# kicik-up.net
KiCad netlist of a schematic drawn in EAGLE
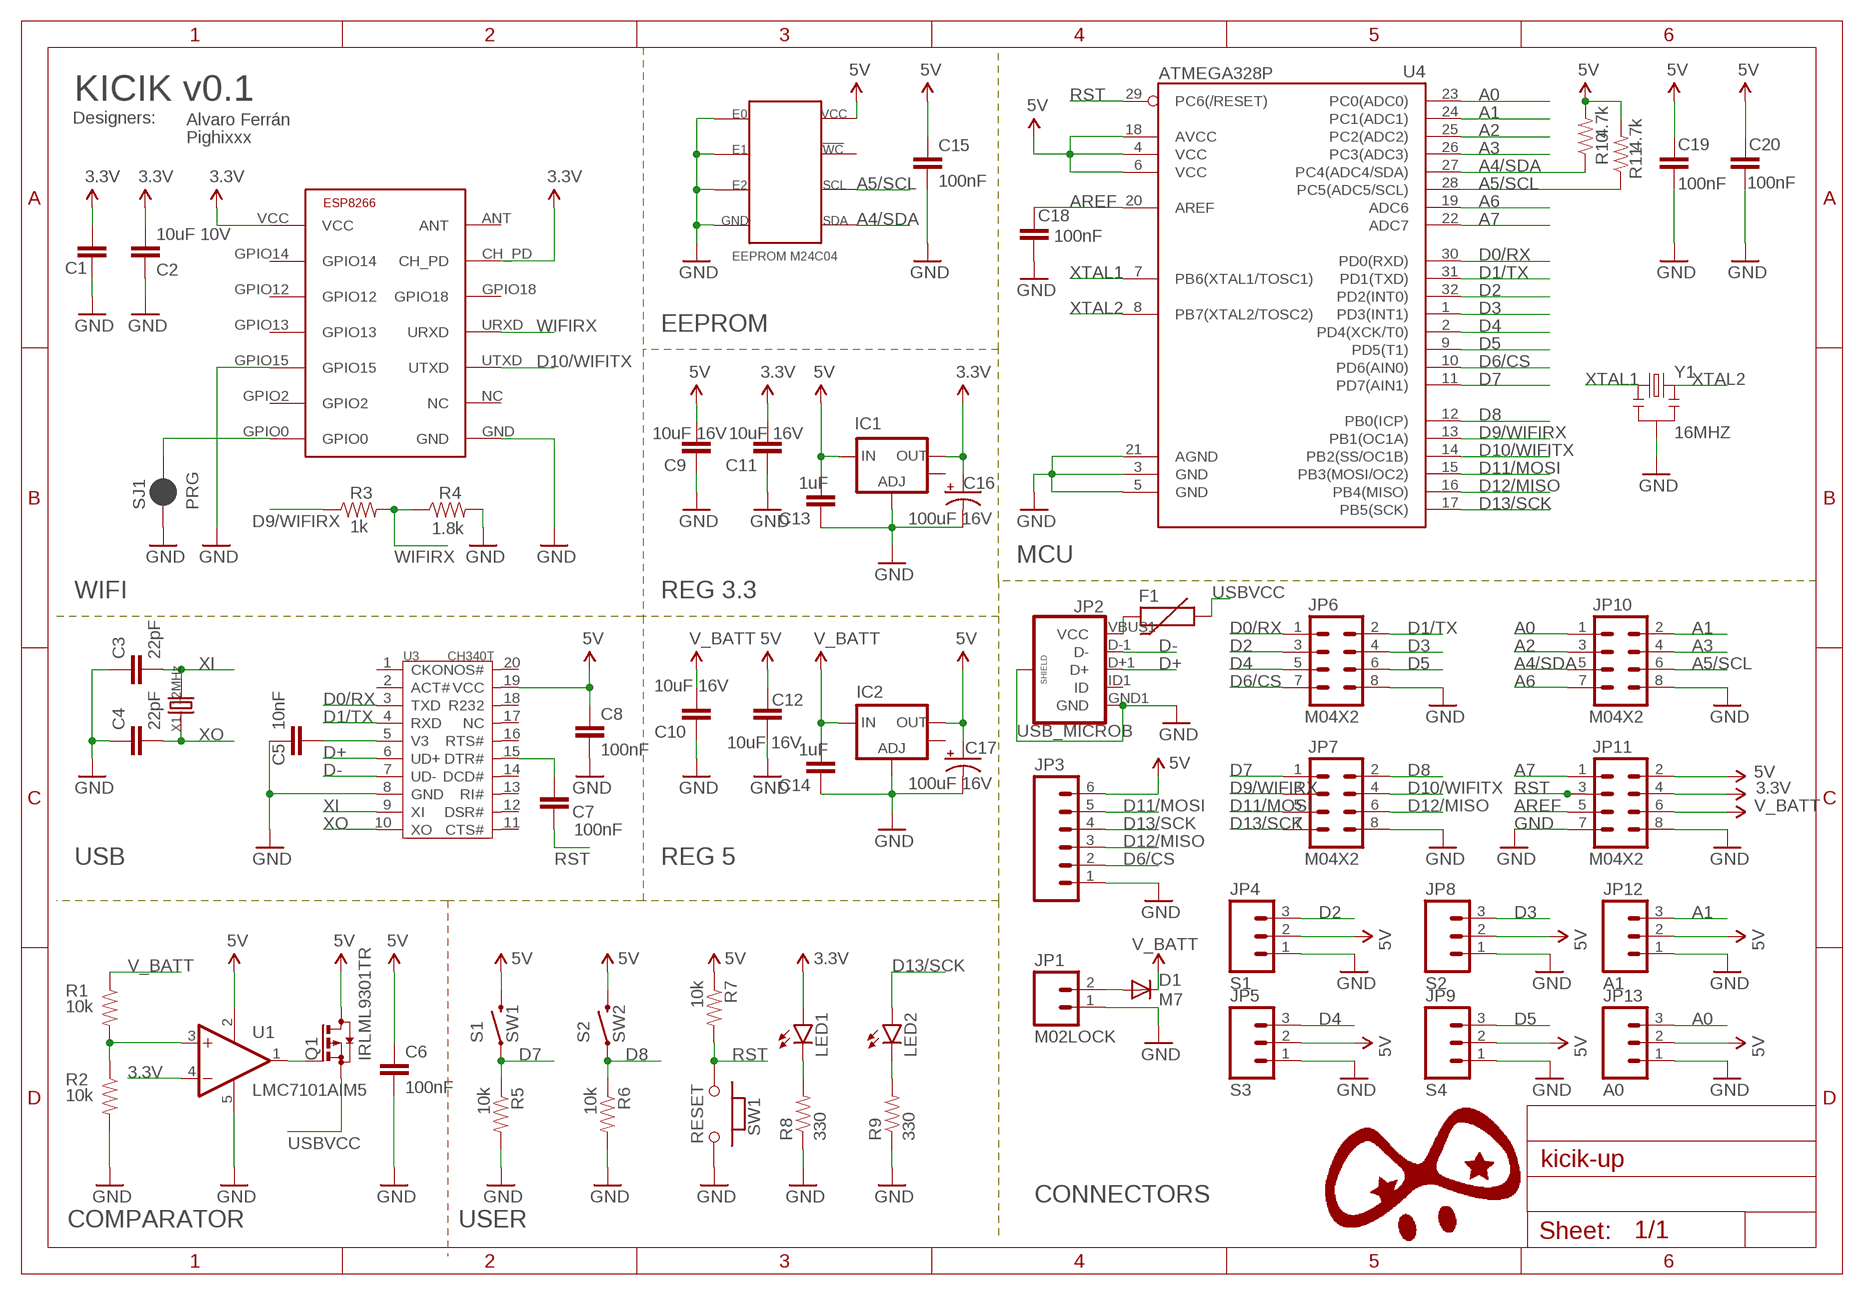
[diagram p0: schematic, sheet 1]

(export (version "E")
  (design (tool "Eeschema 10.0.6"))
  (components
    (comp (ref "C1")
      (value "0.1uF")
      (footprint "eagle-import:0402-CAP")
      (libsource (lib "eagle-import") (part "CAP0402-CAP"))
    )
    (comp (ref "C2")
      (value "10uF 10V")
      (footprint "eagle-import:0402-CAP")
      (libsource (lib "eagle-import") (part "CAP0402-CAP"))
    )
    (comp (ref "C3")
      (value "22pF")
      (footprint "eagle-import:0402-CAP")
      (libsource (lib "eagle-import") (part "CAP0402-CAP"))
    )
    (comp (ref "C4")
      (value "22pF")
      (footprint "eagle-import:0402-CAP")
      (libsource (lib "eagle-import") (part "CAP0402-CAP"))
    )
    (comp (ref "C5")
      (value "10nF")
      (footprint "eagle-import:0402-CAP")
      (libsource (lib "eagle-import") (part "CAP0402-CAP"))
    )
    (comp (ref "C6")
      (value "100nF")
      (footprint "eagle-import:0402-CAP")
      (libsource (lib "eagle-import") (part "CAP0402-CAP"))
    )
    (comp (ref "C7")
      (value "100nF")
      (footprint "eagle-import:0402-CAP")
      (libsource (lib "eagle-import") (part "CAP0402-CAP"))
    )
    (comp (ref "C8")
      (value "100nF")
      (footprint "eagle-import:0402-CAP")
      (libsource (lib "eagle-import") (part "CAP0402-CAP"))
    )
    (comp (ref "C9")
      (value "10uF 16V")
      (footprint "eagle-import:0402-CAP")
      (libsource (lib "eagle-import") (part "CAP0402-CAP"))
    )
    (comp (ref "C10")
      (value "10uF 16V")
      (footprint "eagle-import:0402-CAP")
      (libsource (lib "eagle-import") (part "CAP0402-CAP"))
    )
    (comp (ref "C11")
      (value "10uF 16V")
      (footprint "eagle-import:0402-CAP")
      (libsource (lib "eagle-import") (part "CAP0402-CAP"))
    )
    (comp (ref "C12")
      (value "10uF 16V")
      (footprint "eagle-import:0402-CAP")
      (libsource (lib "eagle-import") (part "CAP0402-CAP"))
    )
    (comp (ref "C13")
      (value "1uF")
      (footprint "eagle-import:0402-CAP")
      (libsource (lib "eagle-import") (part "CAP0402-CAP"))
    )
    (comp (ref "C14")
      (value "1uF")
      (footprint "eagle-import:0402-CAP")
      (libsource (lib "eagle-import") (part "CAP0402-CAP"))
    )
    (comp (ref "C15")
      (value "100nF")
      (footprint "eagle-import:0402-CAP")
      (libsource (lib "eagle-import") (part "CAP0402-CAP"))
    )
    (comp (ref "C16")
      (value "100uF 16V")
      (footprint "eagle-import:PANASONIC_C")
      (libsource (lib "eagle-import") (part "CAP_POLC"))
    )
    (comp (ref "C17")
      (value "100uF 16V")
      (footprint "eagle-import:PANASONIC_C")
      (libsource (lib "eagle-import") (part "CAP_POLC"))
    )
    (comp (ref "C18")
      (value "100nF")
      (footprint "eagle-import:0402-CAP")
      (libsource (lib "eagle-import") (part "CAP0402-CAP"))
    )
    (comp (ref "C19")
      (value "100nF")
      (footprint "eagle-import:0402-CAP")
      (libsource (lib "eagle-import") (part "CAP0402-CAP"))
    )
    (comp (ref "C20")
      (value "100nF")
      (footprint "eagle-import:0402-CAP")
      (libsource (lib "eagle-import") (part "CAP0402-CAP"))
    )
    (comp (ref "D1")
      (value "M7")
      (footprint "eagle-import:SMB")
      (libsource (lib "eagle-import") (part "DIODE-SMB"))
    )
    (comp (ref "F1")
      (value "PTC0603")
      (footprint "eagle-import:0603")
      (libsource (lib "eagle-import") (part "PTC0603"))
    )
    (comp (ref "IC1")
      (value "V_REG_LM1117SOT223")
      (footprint "eagle-import:SOT223")
      (libsource (lib "eagle-import") (part "V_REG_LM1117SOT223"))
    )
    (comp (ref "IC2")
      (value "V_REG_LM1117SOT223")
      (footprint "eagle-import:SOT223")
      (libsource (lib "eagle-import") (part "V_REG_LM1117SOT223"))
    )
    (comp (ref "JP1")
      (value "M02LOCK")
      (footprint "eagle-import:1X02_LOCK")
      (libsource (lib "eagle-import") (part "M02LOCK"))
    )
    (comp (ref "JP2")
      (value "USB_MICROB")
      (footprint "eagle-import:USB-B-MICRO-SMD_V03")
      (libsource (lib "eagle-import") (part "USB_MICROB_PLUGCONN-11752"))
    )
    (comp (ref "JP3")
      (value "M06LOCK")
      (footprint "eagle-import:1X06_LOCK")
      (libsource (lib "eagle-import") (part "M06LOCK"))
    )
    (comp (ref "JP4")
      (value "S1")
      (footprint "eagle-import:1X03_LOCK")
      (libsource (lib "eagle-import") (part "M03LOCK"))
    )
    (comp (ref "JP5")
      (value "S3")
      (footprint "eagle-import:1X03_LOCK")
      (libsource (lib "eagle-import") (part "M03LOCK"))
    )
    (comp (ref "JP6")
      (value "M04X2")
      (footprint "eagle-import:2X4")
      (libsource (lib "eagle-import") (part "M04X2"))
    )
    (comp (ref "JP7")
      (value "M04X2")
      (footprint "eagle-import:2X4")
      (libsource (lib "eagle-import") (part "M04X2"))
    )
    (comp (ref "JP8")
      (value "S2")
      (footprint "eagle-import:1X03_LOCK")
      (libsource (lib "eagle-import") (part "M03LOCK"))
    )
    (comp (ref "JP9")
      (value "S4")
      (footprint "eagle-import:1X03_LOCK")
      (libsource (lib "eagle-import") (part "M03LOCK"))
    )
    (comp (ref "JP10")
      (value "M04X2")
      (footprint "eagle-import:2X4")
      (libsource (lib "eagle-import") (part "M04X2"))
    )
    (comp (ref "JP11")
      (value "M04X2")
      (footprint "eagle-import:2X4")
      (libsource (lib "eagle-import") (part "M04X2"))
    )
    (comp (ref "JP12")
      (value "A1")
      (footprint "eagle-import:1X03_LOCK")
      (libsource (lib "eagle-import") (part "M03LOCK"))
    )
    (comp (ref "JP13")
      (value "A0")
      (footprint "eagle-import:1X03_LOCK")
      (libsource (lib "eagle-import") (part "M03LOCK"))
    )
    (comp (ref "LED1")
      (value "LED0603")
      (footprint "eagle-import:LED-0603")
      (libsource (lib "eagle-import") (part "LED0603"))
    )
    (comp (ref "LED2")
      (value "LED0603")
      (footprint "eagle-import:LED-0603")
      (libsource (lib "eagle-import") (part "LED0603"))
    )
    (comp (ref "M1")
      (value "M24C04")
      (footprint "eagle-import:SO08")
      (libsource (lib "eagle-import") (part "M24C04"))
    )
    (comp (ref "Q1")
      (value "IRLML9301TR")
      (footprint "eagle-import:SOT23")
      (libsource (lib "eagle-import") (part "BSS84"))
    )
    (comp (ref "R1")
      (value "10k")
      (footprint "eagle-import:0402-RES")
      (libsource (lib "eagle-import") (part "RESISTOR0402-RES"))
    )
    (comp (ref "R2")
      (value "10k")
      (footprint "eagle-import:0402-RES")
      (libsource (lib "eagle-import") (part "RESISTOR0402-RES"))
    )
    (comp (ref "R3")
      (value "1k")
      (footprint "eagle-import:0402-RES")
      (libsource (lib "eagle-import") (part "RESISTOR0402-RES"))
    )
    (comp (ref "R4")
      (value "1.8k")
      (footprint "eagle-import:0402-RES")
      (libsource (lib "eagle-import") (part "RESISTOR0402-RES"))
    )
    (comp (ref "R5")
      (value "10k")
      (footprint "eagle-import:0402-RES")
      (libsource (lib "eagle-import") (part "RESISTOR0402-RES"))
    )
    (comp (ref "R6")
      (value "10k")
      (footprint "eagle-import:0402-RES")
      (libsource (lib "eagle-import") (part "RESISTOR0402-RES"))
    )
    (comp (ref "R7")
      (value "10k")
      (footprint "eagle-import:0402-RES")
      (libsource (lib "eagle-import") (part "RESISTOR0402-RES"))
    )
    (comp (ref "R8")
      (value "330")
      (footprint "eagle-import:0402-RES")
      (libsource (lib "eagle-import") (part "RESISTOR0402-RES"))
    )
    (comp (ref "R9")
      (value "330")
      (footprint "eagle-import:0402-RES")
      (libsource (lib "eagle-import") (part "RESISTOR0402-RES"))
    )
    (comp (ref "R10")
      (value "4.7k")
      (footprint "eagle-import:0402-RES")
      (libsource (lib "eagle-import") (part "RESISTOR0402-RES"))
    )
    (comp (ref "R11")
      (value "4.7k")
      (footprint "eagle-import:0402-RES")
      (libsource (lib "eagle-import") (part "RESISTOR0402-RES"))
    )
    (comp (ref "S1")
      (value "SW1")
      (footprint "eagle-import:TACTILE-PTH-SIDEEZ")
      (libsource (lib "eagle-import") (part "SWITCH-MOMENTARY-2SIDE_EZ"))
    )
    (comp (ref "S2")
      (value "SW2")
      (footprint "eagle-import:TACTILE-PTH-SIDEEZ")
      (libsource (lib "eagle-import") (part "SWITCH-MOMENTARY-2SIDE_EZ"))
    )
    (comp (ref "SJ1")
      (value "PRG")
      (footprint "eagle-import:PAD-JUMPER-2-NC_BY_PASTE_YES_SILK")
      (libsource (lib "eagle-import") (part "JUMPER-PAD-2-NC_BY_PASTE"))
    )
    (comp (ref "SW1")
      (value "RESET")
      (footprint "eagle-import:157SW")
      (libsource (lib "eagle-import") (part "PB157"))
    )
    (comp (ref "U1")
      (value "LMC7101AIM5")
      (footprint "eagle-import:SOT23-5")
      (libsource (lib "eagle-import") (part "LMC7101AIM5"))
    )
    (comp (ref "U2")
      (value "ESP8266")
      (footprint "eagle-import:ESP-03")
      (libsource (lib "eagle-import") (part "ESP8266"))
    )
    (comp (ref "U3")
      (value "CH340T")
      (footprint "eagle-import:SSOP20")
      (libsource (lib "eagle-import") (part "CH340T"))
    )
    (comp (ref "U4")
      (value "ATMEGA328P")
      (footprint "eagle-import:TQFP32-08")
      (libsource (lib "eagle-import") (part "ATMEGA328_SMT"))
    )
    (comp (ref "X1")
      (value "12MHz")
      (footprint "eagle-import:2P-SMD-5X3.2")
      (libsource (lib "eagle-import") (part "CRYSTAL'5032'"))
    )
    (comp (ref "Y1")
      (value "16MHZ")
      (footprint "eagle-import:RESONATOR-SMD")
      (libsource (lib "eagle-import") (part "RESONATOR16MHZ"))
    )
  )
  (nets
    (net (code "1") (name "/A0") (class "Default")
      (node (ref "JP10") (pin "1") (pinfunction "1_1") (pintype "passive"))
      (node (ref "JP13") (pin "3") (pinfunction "3_3") (pintype "passive"))
      (node (ref "U4") (pin "23") (pinfunction "PC0(ADC0)_23") (pintype "bidirectional"))
    )
    (net (code "2") (name "/A1") (class "Default")
      (node (ref "JP10") (pin "2") (pinfunction "2_2") (pintype "passive"))
      (node (ref "JP12") (pin "3") (pinfunction "3_3") (pintype "passive"))
      (node (ref "U4") (pin "24") (pinfunction "PC1(ADC1)_24") (pintype "bidirectional"))
    )
    (net (code "3") (name "/A2") (class "Default")
      (node (ref "JP10") (pin "3") (pinfunction "3_3") (pintype "passive"))
      (node (ref "U4") (pin "25") (pinfunction "PC2(ADC2)_25") (pintype "bidirectional"))
    )
    (net (code "4") (name "/A3") (class "Default")
      (node (ref "JP10") (pin "4") (pinfunction "4_4") (pintype "passive"))
      (node (ref "U4") (pin "26") (pinfunction "PC3(ADC3)_26") (pintype "bidirectional"))
    )
    (net (code "5") (name "/A4{slash}SDA") (class "Default")
      (node (ref "JP10") (pin "5") (pinfunction "5_5") (pintype "passive"))
      (node (ref "M1") (pin "5") (pinfunction "SDA_5") (pintype "bidirectional"))
      (node (ref "R10") (pin "1") (pinfunction "1_1") (pintype "passive"))
      (node (ref "U4") (pin "27") (pinfunction "PC4(ADC4/SDA)_27") (pintype "bidirectional"))
    )
    (net (code "6") (name "/A5{slash}SCL") (class "Default")
      (node (ref "JP10") (pin "6") (pinfunction "6_6") (pintype "passive"))
      (node (ref "M1") (pin "6") (pinfunction "SCL_6") (pintype "bidirectional"))
      (node (ref "R11") (pin "1") (pinfunction "1_1") (pintype "passive"))
      (node (ref "U4") (pin "28") (pinfunction "PC5(ADC5/SCL)_28") (pintype "bidirectional"))
    )
    (net (code "7") (name "/A6") (class "Default")
      (node (ref "JP10") (pin "7") (pinfunction "7_7") (pintype "passive"))
      (node (ref "U4") (pin "19") (pinfunction "ADC6_19") (pintype "bidirectional"))
    )
    (net (code "8") (name "/A7") (class "Default")
      (node (ref "JP11") (pin "1") (pinfunction "1_1") (pintype "passive"))
      (node (ref "U4") (pin "22") (pinfunction "ADC7_22") (pintype "bidirectional"))
    )
    (net (code "9") (name "/AREF") (class "Default")
      (node (ref "C18") (pin "1") (pinfunction "1_1") (pintype "passive"))
      (node (ref "JP11") (pin "5") (pinfunction "5_5") (pintype "passive"))
      (node (ref "U4") (pin "20") (pinfunction "AREF_20") (pintype "bidirectional"))
    )
    (net (code "10") (name "/D+") (class "Default")
      (node (ref "JP2") (pin "D+1") (pinfunction "D+_D+1") (pintype "bidirectional"))
      (node (ref "U3") (pin "6") (pinfunction "UD+_6") (pintype "bidirectional"))
    )
    (net (code "11") (name "/D-") (class "Default")
      (node (ref "JP2") (pin "D-1") (pinfunction "D-_D-1") (pintype "bidirectional"))
      (node (ref "U3") (pin "7") (pinfunction "UD-_7") (pintype "bidirectional"))
    )
    (net (code "12") (name "/D0{slash}RX") (class "Default")
      (node (ref "JP6") (pin "1") (pinfunction "1_1") (pintype "passive"))
      (node (ref "U3") (pin "3") (pinfunction "TXD_3") (pintype "output"))
      (node (ref "U4") (pin "30") (pinfunction "PD0(RXD)_30") (pintype "bidirectional"))
    )
    (net (code "13") (name "/D1{slash}TX") (class "Default")
      (node (ref "JP6") (pin "2") (pinfunction "2_2") (pintype "passive"))
      (node (ref "U3") (pin "4") (pinfunction "RXD_4") (pintype "input"))
      (node (ref "U4") (pin "31") (pinfunction "PD1(TXD)_31") (pintype "bidirectional"))
    )
    (net (code "14") (name "/D2") (class "Default")
      (node (ref "JP4") (pin "3") (pinfunction "3_3") (pintype "passive"))
      (node (ref "JP6") (pin "3") (pinfunction "3_3") (pintype "passive"))
      (node (ref "U4") (pin "32") (pinfunction "PD2(INT0)_32") (pintype "bidirectional"))
    )
    (net (code "15") (name "/D3") (class "Default")
      (node (ref "JP6") (pin "4") (pinfunction "4_4") (pintype "passive"))
      (node (ref "JP8") (pin "3") (pinfunction "3_3") (pintype "passive"))
      (node (ref "U4") (pin "1") (pinfunction "PD3(INT1)_1") (pintype "bidirectional"))
    )
    (net (code "16") (name "/D4") (class "Default")
      (node (ref "JP5") (pin "3") (pinfunction "3_3") (pintype "passive"))
      (node (ref "JP6") (pin "5") (pinfunction "5_5") (pintype "passive"))
      (node (ref "U4") (pin "2") (pinfunction "PD4(XCK/T0)_2") (pintype "bidirectional"))
    )
    (net (code "17") (name "/D5") (class "Default")
      (node (ref "JP6") (pin "6") (pinfunction "6_6") (pintype "passive"))
      (node (ref "JP9") (pin "3") (pinfunction "3_3") (pintype "passive"))
      (node (ref "U4") (pin "9") (pinfunction "PD5(T1)_9") (pintype "bidirectional"))
    )
    (net (code "18") (name "/D6{slash}CS") (class "Default")
      (node (ref "JP3") (pin "2") (pinfunction "2_2") (pintype "passive"))
      (node (ref "JP6") (pin "7") (pinfunction "7_7") (pintype "passive"))
      (node (ref "U4") (pin "10") (pinfunction "PD6(AIN0)_10") (pintype "bidirectional"))
    )
    (net (code "19") (name "/D7") (class "Default")
      (node (ref "JP7") (pin "1") (pinfunction "1_1") (pintype "passive"))
      (node (ref "R5") (pin "1") (pinfunction "1_1") (pintype "passive"))
      (node (ref "S1") (pin "1") (pinfunction "1_1") (pintype "passive"))
      (node (ref "U4") (pin "11") (pinfunction "PD7(AIN1)_11") (pintype "bidirectional"))
    )
    (net (code "20") (name "/D8") (class "Default")
      (node (ref "JP7") (pin "2") (pinfunction "2_2") (pintype "passive"))
      (node (ref "R6") (pin "1") (pinfunction "1_1") (pintype "passive"))
      (node (ref "S2") (pin "1") (pinfunction "1_1") (pintype "passive"))
      (node (ref "U4") (pin "12") (pinfunction "PB0(ICP)_12") (pintype "bidirectional"))
    )
    (net (code "21") (name "/D9{slash}WIFIRX") (class "Default")
      (node (ref "JP7") (pin "3") (pinfunction "3_3") (pintype "passive"))
      (node (ref "R3") (pin "1") (pinfunction "1_1") (pintype "passive"))
      (node (ref "U4") (pin "13") (pinfunction "PB1(OC1A)_13") (pintype "bidirectional"))
    )
    (net (code "22") (name "/D10{slash}WIFITX") (class "Default")
      (node (ref "JP7") (pin "4") (pinfunction "4_4") (pintype "passive"))
      (node (ref "U2") (pin "UTXD") (pinfunction "UTXD_UTXD") (pintype "bidirectional"))
      (node (ref "U4") (pin "14") (pinfunction "PB2(SS/OC1B)_14") (pintype "bidirectional"))
    )
    (net (code "23") (name "/D11{slash}MOSI") (class "Default")
      (node (ref "JP3") (pin "5") (pinfunction "5_5") (pintype "passive"))
      (node (ref "JP7") (pin "5") (pinfunction "5_5") (pintype "passive"))
      (node (ref "U4") (pin "15") (pinfunction "PB3(MOSI/OC2)_15") (pintype "bidirectional"))
    )
    (net (code "24") (name "/D12{slash}MISO") (class "Default")
      (node (ref "JP3") (pin "3") (pinfunction "3_3") (pintype "passive"))
      (node (ref "JP7") (pin "6") (pinfunction "6_6") (pintype "passive"))
      (node (ref "U4") (pin "16") (pinfunction "PB4(MISO)_16") (pintype "bidirectional"))
    )
    (net (code "25") (name "/D13{slash}SCK") (class "Default")
      (node (ref "JP3") (pin "4") (pinfunction "4_4") (pintype "passive"))
      (node (ref "JP7") (pin "7") (pinfunction "7_7") (pintype "passive"))
      (node (ref "LED2") (pin "A") (pinfunction "A_A") (pintype "passive"))
      (node (ref "U4") (pin "17") (pinfunction "PB5(SCK)_17") (pintype "bidirectional"))
    )
    (net (code "26") (name "/NOS#") (class "Default")
      (node (ref "U3") (pin "20") (pinfunction "NOS#_20") (pintype "power_in"))
    )
    (net (code "27") (name "/RST") (class "Default")
      (node (ref "C7") (pin "2") (pinfunction "2_2") (pintype "passive"))
      (node (ref "JP11") (pin "3") (pinfunction "3_3") (pintype "passive"))
      (node (ref "R7") (pin "2") (pinfunction "2_2") (pintype "passive"))
      (node (ref "SW1") (pin "1") (pinfunction "1_1") (pintype "passive"))
      (node (ref "U4") (pin "29") (pinfunction "PC6(/RESET)_29") (pintype "bidirectional"))
    )
    (net (code "28") (name "/USBVCC") (class "Default")
      (node (ref "F1") (pin "1") (pinfunction "1_1") (pintype "bidirectional"))
      (node (ref "Q1") (pin "2") (pinfunction "S_2") (pintype "passive"))
    )
    (net (code "29") (name "/WIFIRX") (class "Default")
      (node (ref "R3") (pin "2") (pinfunction "2_2") (pintype "passive"))
      (node (ref "R4") (pin "1") (pinfunction "1_1") (pintype "passive"))
      (node (ref "U2") (pin "URXD") (pinfunction "URXD_URXD") (pintype "bidirectional"))
    )
    (net (code "30") (name "/XI") (class "Default")
      (node (ref "C3") (pin "2") (pinfunction "2_2") (pintype "passive"))
      (node (ref "U3") (pin "9") (pinfunction "XI_9") (pintype "input"))
      (node (ref "X1") (pin "2") (pinfunction "2_2") (pintype "passive"))
    )
    (net (code "31") (name "/XO") (class "Default")
      (node (ref "C4") (pin "2") (pinfunction "2_2") (pintype "passive"))
      (node (ref "U3") (pin "10") (pinfunction "XO_10") (pintype "output"))
      (node (ref "X1") (pin "1") (pinfunction "1_1") (pintype "passive"))
    )
    (net (code "32") (name "/XTAL1") (class "Default")
      (node (ref "U4") (pin "7") (pinfunction "PB6(XTAL1/TOSC1)_7") (pintype "bidirectional"))
      (node (ref "Y1") (pin "1") (pinfunction "1_1") (pintype "passive"))
    )
    (net (code "33") (name "/XTAL2") (class "Default")
      (node (ref "U4") (pin "8") (pinfunction "PB7(XTAL2/TOSC2)_8") (pintype "bidirectional"))
      (node (ref "Y1") (pin "3") (pinfunction "3_3") (pintype "passive"))
    )
    (net (code "34") (name "3.3V") (class "Default")
      (node (ref "C1") (pin "2") (pinfunction "2_2") (pintype "passive"))
      (node (ref "C11") (pin "2") (pinfunction "2_2") (pintype "passive"))
      (node (ref "C16") (pin "+") (pinfunction "+_+") (pintype "passive"))
      (node (ref "C2") (pin "2") (pinfunction "2_2") (pintype "passive"))
      (node (ref "IC1") (pin "2") (pinfunction "OUT_2") (pintype "output"))
      (node (ref "JP11") (pin "4") (pinfunction "4_4") (pintype "passive"))
      (node (ref "LED1") (pin "A") (pinfunction "A_A") (pintype "passive"))
      (node (ref "U1") (pin "4") (pinfunction "-IN_4") (pintype "input"))
      (node (ref "U2") (pin "CH_PD") (pinfunction "CH_PD_CH_PD") (pintype "bidirectional"))
      (node (ref "U2") (pin "VCC") (pinfunction "VCC_VCC") (pintype "bidirectional"))
    )
    (net (code "35") (name "5V") (class "Default")
      (node (ref "C12") (pin "2") (pinfunction "2_2") (pintype "passive"))
      (node (ref "C13") (pin "2") (pinfunction "2_2") (pintype "passive"))
      (node (ref "C15") (pin "1") (pinfunction "1_1") (pintype "passive"))
      (node (ref "C17") (pin "+") (pinfunction "+_+") (pintype "passive"))
      (node (ref "C19") (pin "1") (pinfunction "1_1") (pintype "passive"))
      (node (ref "C20") (pin "1") (pinfunction "1_1") (pintype "passive"))
      (node (ref "C6") (pin "1") (pinfunction "1_1") (pintype "passive"))
      (node (ref "C8") (pin "1") (pinfunction "1_1") (pintype "passive"))
      (node (ref "C9") (pin "2") (pinfunction "2_2") (pintype "passive"))
      (node (ref "IC1") (pin "3") (pinfunction "IN_3") (pintype "input"))
      (node (ref "IC2") (pin "2") (pinfunction "OUT_2") (pintype "output"))
      (node (ref "JP11") (pin "2") (pinfunction "2_2") (pintype "passive"))
      (node (ref "JP12") (pin "2") (pinfunction "2_2") (pintype "passive"))
      (node (ref "JP13") (pin "2") (pinfunction "2_2") (pintype "passive"))
      (node (ref "JP3") (pin "6") (pinfunction "6_6") (pintype "passive"))
      (node (ref "JP4") (pin "2") (pinfunction "2_2") (pintype "passive"))
      (node (ref "JP5") (pin "2") (pinfunction "2_2") (pintype "passive"))
      (node (ref "JP8") (pin "2") (pinfunction "2_2") (pintype "passive"))
      (node (ref "JP9") (pin "2") (pinfunction "2_2") (pintype "passive"))
      (node (ref "M1") (pin "8") (pinfunction "VCC_8") (pintype "bidirectional"))
      (node (ref "Q1") (pin "3") (pinfunction "D_3") (pintype "passive"))
      (node (ref "R10") (pin "2") (pinfunction "2_2") (pintype "passive"))
      (node (ref "R11") (pin "2") (pinfunction "2_2") (pintype "passive"))
      (node (ref "R7") (pin "1") (pinfunction "1_1") (pintype "passive"))
      (node (ref "S1") (pin "2") (pinfunction "2_2") (pintype "passive"))
      (node (ref "S2") (pin "2") (pinfunction "2_2") (pintype "passive"))
      (node (ref "U1") (pin "2") (pinfunction "V+_2") (pintype "power_in"))
      (node (ref "U3") (pin "19") (pinfunction "VCC_19") (pintype "power_in"))
      (node (ref "U4") (pin "18") (pinfunction "AVCC_18") (pintype "bidirectional"))
      (node (ref "U4") (pin "4") (pinfunction "VCC_4") (pintype "bidirectional"))
      (node (ref "U4") (pin "6") (pinfunction "VCC_6") (pintype "bidirectional"))
    )
    (net (code "36") (name "GND") (class "Default")
      (node (ref "C1") (pin "1") (pinfunction "1_1") (pintype "passive"))
      (node (ref "C10") (pin "1") (pinfunction "1_1") (pintype "passive"))
      (node (ref "C11") (pin "1") (pinfunction "1_1") (pintype "passive"))
      (node (ref "C12") (pin "1") (pinfunction "1_1") (pintype "passive"))
      (node (ref "C13") (pin "1") (pinfunction "1_1") (pintype "passive"))
      (node (ref "C14") (pin "1") (pinfunction "1_1") (pintype "passive"))
      (node (ref "C15") (pin "2") (pinfunction "2_2") (pintype "passive"))
      (node (ref "C16") (pin "-") (pinfunction "-_-") (pintype "passive"))
      (node (ref "C17") (pin "-") (pinfunction "-_-") (pintype "passive"))
      (node (ref "C18") (pin "2") (pinfunction "2_2") (pintype "passive"))
      (node (ref "C19") (pin "2") (pinfunction "2_2") (pintype "passive"))
      (node (ref "C2") (pin "1") (pinfunction "1_1") (pintype "passive"))
      (node (ref "C20") (pin "2") (pinfunction "2_2") (pintype "passive"))
      (node (ref "C3") (pin "1") (pinfunction "1_1") (pintype "passive"))
      (node (ref "C4") (pin "1") (pinfunction "1_1") (pintype "passive"))
      (node (ref "C5") (pin "1") (pinfunction "1_1") (pintype "passive"))
      (node (ref "C6") (pin "2") (pinfunction "2_2") (pintype "passive"))
      (node (ref "C8") (pin "2") (pinfunction "2_2") (pintype "passive"))
      (node (ref "C9") (pin "1") (pinfunction "1_1") (pintype "passive"))
      (node (ref "IC1") (pin "1") (pinfunction "ADJ_1") (pintype "input"))
      (node (ref "IC2") (pin "1") (pinfunction "ADJ_1") (pintype "input"))
      (node (ref "JP1") (pin "1") (pinfunction "1_1") (pintype "passive"))
      (node (ref "JP10") (pin "8") (pinfunction "8_8") (pintype "passive"))
      (node (ref "JP11") (pin "7") (pinfunction "7_7") (pintype "passive"))
      (node (ref "JP11") (pin "8") (pinfunction "8_8") (pintype "passive"))
      (node (ref "JP12") (pin "1") (pinfunction "1_1") (pintype "passive"))
      (node (ref "JP13") (pin "1") (pinfunction "1_1") (pintype "passive"))
      (node (ref "JP2") (pin "GND1") (pinfunction "GND_GND1") (pintype "bidirectional"))
      (node (ref "JP2") (pin "SHIELD1") (pinfunction "SHIELD_SHIELD1") (pintype "bidirectional"))
      (node (ref "JP2") (pin "SHIELD2") (pinfunction "SHIELD_SHIELD2") (pintype "bidirectional"))
      (node (ref "JP2") (pin "SHIELD3") (pinfunction "SHIELD_SHIELD3") (pintype "bidirectional"))
      (node (ref "JP3") (pin "1") (pinfunction "1_1") (pintype "passive"))
      (node (ref "JP4") (pin "1") (pinfunction "1_1") (pintype "passive"))
      (node (ref "JP5") (pin "1") (pinfunction "1_1") (pintype "passive"))
      (node (ref "JP6") (pin "8") (pinfunction "8_8") (pintype "passive"))
      (node (ref "JP7") (pin "8") (pinfunction "8_8") (pintype "passive"))
      (node (ref "JP8") (pin "1") (pinfunction "1_1") (pintype "passive"))
      (node (ref "JP9") (pin "1") (pinfunction "1_1") (pintype "passive"))
      (node (ref "M1") (pin "1") (pinfunction "E0_1") (pintype "bidirectional"))
      (node (ref "M1") (pin "2") (pinfunction "E1_2") (pintype "bidirectional"))
      (node (ref "M1") (pin "3") (pinfunction "E2_3") (pintype "bidirectional"))
      (node (ref "M1") (pin "4") (pinfunction "GND_4") (pintype "bidirectional"))
      (node (ref "R2") (pin "2") (pinfunction "2_2") (pintype "passive"))
      (node (ref "R4") (pin "2") (pinfunction "2_2") (pintype "passive"))
      (node (ref "R5") (pin "2") (pinfunction "2_2") (pintype "passive"))
      (node (ref "R6") (pin "2") (pinfunction "2_2") (pintype "passive"))
      (node (ref "R8") (pin "1") (pinfunction "1_1") (pintype "passive"))
      (node (ref "R9") (pin "1") (pinfunction "1_1") (pintype "passive"))
      (node (ref "SJ1") (pin "1") (pinfunction "1_1") (pintype "passive"))
      (node (ref "SW1") (pin "2") (pinfunction "2_2") (pintype "passive"))
      (node (ref "U1") (pin "5") (pinfunction "V-_5") (pintype "power_in"))
      (node (ref "U2") (pin "GND") (pinfunction "GND_GND") (pintype "bidirectional"))
      (node (ref "U2") (pin "GPIO15") (pinfunction "GPIO15_GPIO15") (pintype "bidirectional"))
      (node (ref "U3") (pin "8") (pinfunction "GND_8") (pintype "power_in"))
      (node (ref "U4") (pin "21") (pinfunction "AGND_21") (pintype "bidirectional"))
      (node (ref "U4") (pin "3") (pinfunction "GND_3") (pintype "bidirectional"))
      (node (ref "U4") (pin "5") (pinfunction "GND_5") (pintype "bidirectional"))
      (node (ref "Y1") (pin "2") (pinfunction "2_2") (pintype "passive"))
    )
    (net (code "37") (name "Net-(D1-PadA)") (class "Default")
      (node (ref "D1") (pin "A") (pinfunction "A_A") (pintype "passive"))
      (node (ref "JP1") (pin "2") (pinfunction "2_2") (pintype "passive"))
    )
    (net (code "38") (name "Net-(JP2-VCC)") (class "Default")
      (node (ref "F1") (pin "2") (pinfunction "2_2") (pintype "bidirectional"))
      (node (ref "JP2") (pin "VBUS1") (pinfunction "VCC_VBUS1") (pintype "bidirectional"))
    )
    (net (code "39") (name "Net-(LED1-PadC)") (class "Default")
      (node (ref "LED1") (pin "C") (pinfunction "C_C") (pintype "passive"))
      (node (ref "R8") (pin "2") (pinfunction "2_2") (pintype "passive"))
    )
    (net (code "40") (name "Net-(LED2-PadC)") (class "Default")
      (node (ref "LED2") (pin "C") (pinfunction "C_C") (pintype "passive"))
      (node (ref "R9") (pin "2") (pinfunction "2_2") (pintype "passive"))
    )
    (net (code "41") (name "Net-(Q1-G)") (class "Default")
      (node (ref "Q1") (pin "1") (pinfunction "G_1") (pintype "passive"))
      (node (ref "U1") (pin "1") (pinfunction "OUT_1") (pintype "output"))
    )
    (net (code "42") (name "Net-(SJ1-Pad2)") (class "Default")
      (node (ref "SJ1") (pin "2") (pinfunction "2_2") (pintype "passive"))
      (node (ref "U2") (pin "GPIO0") (pinfunction "GPIO0_GPIO0") (pintype "bidirectional"))
    )
    (net (code "43") (name "Net-(U1-+IN)") (class "Default")
      (node (ref "R1") (pin "2") (pinfunction "2_2") (pintype "passive"))
      (node (ref "R2") (pin "1") (pinfunction "1_1") (pintype "passive"))
      (node (ref "U1") (pin "3") (pinfunction "+IN_3") (pintype "input"))
    )
    (net (code "44") (name "Net-(U3-DTR#)") (class "Default")
      (node (ref "C7") (pin "1") (pinfunction "1_1") (pintype "passive"))
      (node (ref "U3") (pin "15") (pinfunction "DTR#_15") (pintype "output"))
    )
    (net (code "45") (name "Net-(U3-V3)") (class "Default")
      (node (ref "C5") (pin "2") (pinfunction "2_2") (pintype "passive"))
      (node (ref "U3") (pin "5") (pinfunction "V3_5") (pintype "power_in"))
    )
    (net (code "46") (name "V_BATT") (class "Default")
      (node (ref "C10") (pin "2") (pinfunction "2_2") (pintype "passive"))
      (node (ref "C14") (pin "2") (pinfunction "2_2") (pintype "passive"))
      (node (ref "D1") (pin "C") (pinfunction "C_C") (pintype "passive"))
      (node (ref "IC2") (pin "3") (pinfunction "IN_3") (pintype "input"))
      (node (ref "JP11") (pin "6") (pinfunction "6_6") (pintype "passive"))
      (node (ref "R1") (pin "1") (pinfunction "1_1") (pintype "passive"))
    )
    (net (code "47") (name "unconnected-(IC1-OUT-Pad4)") (class "Default")
      (node (ref "IC1") (pin "4") (pinfunction "OUT_4") (pintype "output"))
    )
    (net (code "48") (name "unconnected-(IC2-OUT-Pad4)") (class "Default")
      (node (ref "IC2") (pin "4") (pinfunction "OUT_4") (pintype "output"))
    )
    (net (code "49") (name "unconnected-(JP2-ID-PadID1)") (class "Default")
      (node (ref "JP2") (pin "ID1") (pinfunction "ID_ID1") (pintype "bidirectional"))
    )
    (net (code "50") (name "unconnected-(M1-~{WC}-Pad7)") (class "Default")
      (node (ref "M1") (pin "7") (pinfunction "~{WC}_7") (pintype "bidirectional"))
    )
    (net (code "51") (name "unconnected-(U2-PadANT)") (class "Default")
      (node (ref "U2") (pin "ANT") (pinfunction "ANT_ANT") (pintype "bidirectional"))
    )
    (net (code "52") (name "unconnected-(U2-PadGPIO2)") (class "Default")
      (node (ref "U2") (pin "GPIO2") (pinfunction "GPIO2_GPIO2") (pintype "bidirectional"))
    )
    (net (code "53") (name "unconnected-(U2-PadGPIO12)") (class "Default")
      (node (ref "U2") (pin "GPIO12") (pinfunction "GPIO12_GPIO12") (pintype "bidirectional"))
    )
    (net (code "54") (name "unconnected-(U2-PadGPIO13)") (class "Default")
      (node (ref "U2") (pin "GPIO13") (pinfunction "GPIO13_GPIO13") (pintype "bidirectional"))
    )
    (net (code "55") (name "unconnected-(U2-PadGPIO14)") (class "Default")
      (node (ref "U2") (pin "GPIO14") (pinfunction "GPIO14_GPIO14") (pintype "bidirectional"))
    )
    (net (code "56") (name "unconnected-(U2-PadGPIO18)") (class "Default")
      (node (ref "U2") (pin "GPIO18") (pinfunction "GPIO18_GPIO18") (pintype "bidirectional"))
    )
    (net (code "57") (name "unconnected-(U2-PadNC)") (class "Default")
      (node (ref "U2") (pin "NC") (pinfunction "NC_NC") (pintype "bidirectional"))
    )
    (net (code "58") (name "unconnected-(U3-ACT#-Pad2)") (class "Default")
      (node (ref "U3") (pin "2") (pinfunction "ACT#_2") (pintype "output"))
    )
    (net (code "59") (name "unconnected-(U3-CKO-Pad1)") (class "Default")
      (node (ref "U3") (pin "1") (pinfunction "CKO_1") (pintype "output"))
    )
    (net (code "60") (name "unconnected-(U3-CTS#-Pad11)") (class "Default")
      (node (ref "U3") (pin "11") (pinfunction "CTS#_11") (pintype "input"))
    )
    (net (code "61") (name "unconnected-(U3-DCD#-Pad14)") (class "Default")
      (node (ref "U3") (pin "14") (pinfunction "DCD#_14") (pintype "input"))
    )
    (net (code "62") (name "unconnected-(U3-DSR#-Pad12)") (class "Default")
      (node (ref "U3") (pin "12") (pinfunction "DSR#_12") (pintype "input"))
    )
    (net (code "63") (name "unconnected-(U3-NC-Pad17)") (class "Default")
      (node (ref "U3") (pin "17") (pinfunction "NC_17") (pintype "no_connect"))
    )
    (net (code "64") (name "unconnected-(U3-R232-Pad18)") (class "Default")
      (node (ref "U3") (pin "18") (pinfunction "R232_18") (pintype "input"))
    )
    (net (code "65") (name "unconnected-(U3-RI#-Pad13)") (class "Default")
      (node (ref "U3") (pin "13") (pinfunction "RI#_13") (pintype "input"))
    )
    (net (code "66") (name "unconnected-(U3-RTS#-Pad16)") (class "Default")
      (node (ref "U3") (pin "16") (pinfunction "RTS#_16") (pintype "output"))
    )
  )
)
